# Core.net
KiCad netlist of a schematic drawn in Altium Designer
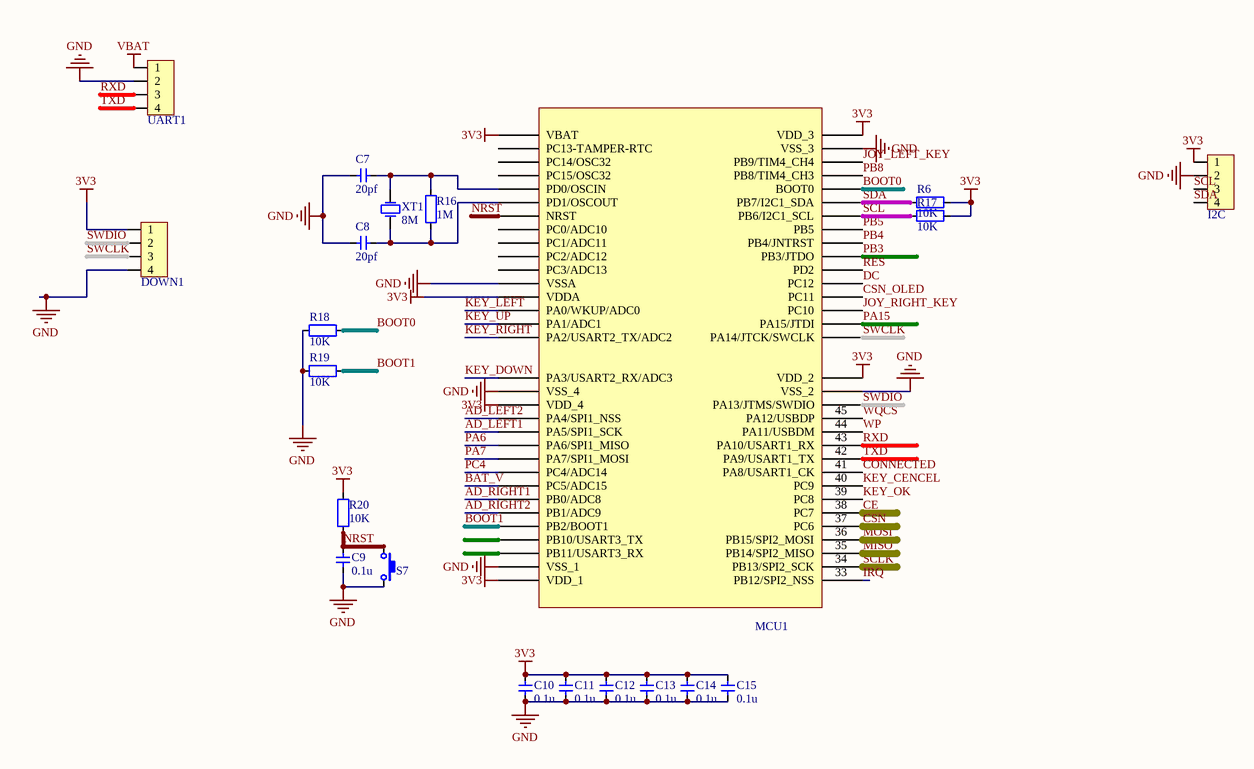
[diagram p0: Core.SchDoc]

(export (version "E")
  (design (tool "Eeschema 10.0.6"))
  (components
    (comp (ref "C7")
      (value "20pf")
      (footprint "PCB_PassiveCap:CAP_0603")
      (description "Capacitor")
      (fields (field (name "Comment") "Cap_0603"))
      (libsource (lib "SCH_Passive") (part "Cap_0603"))
    )
    (comp (ref "C8")
      (value "20pf")
      (footprint "PCB_PassiveCap:CAP_0603")
      (description "Capacitor")
      (fields (field (name "Comment") "Cap_0603"))
      (libsource (lib "SCH_Passive") (part "Cap_0603"))
    )
    (comp (ref "C9")
      (value "0.1u")
      (footprint "PCB_PassiveCap:CAP_0603")
      (description "Capacitor")
      (fields (field (name "Comment") "Cap_0603"))
      (libsource (lib "SCH_Passive") (part "Cap_0603"))
    )
    (comp (ref "C10")
      (value "0.1u")
      (footprint "PCB_PassiveCap:CAP_0603")
      (description "Capacitor")
      (fields (field (name "Comment") "Cap_0603"))
      (libsource (lib "SCH_Passive") (part "Cap_0603"))
    )
    (comp (ref "C11")
      (value "0.1u")
      (footprint "PCB_PassiveCap:CAP_0603")
      (description "Capacitor")
      (fields (field (name "Comment") "Cap_0603"))
      (libsource (lib "SCH_Passive") (part "Cap_0603"))
    )
    (comp (ref "C12")
      (value "0.1u")
      (footprint "PCB_PassiveCap:CAP_0603")
      (description "Capacitor")
      (fields (field (name "Comment") "Cap_0603"))
      (libsource (lib "SCH_Passive") (part "Cap_0603"))
    )
    (comp (ref "C13")
      (value "0.1u")
      (footprint "PCB_PassiveCap:CAP_0603")
      (description "Capacitor")
      (fields (field (name "Comment") "Cap_0603"))
      (libsource (lib "SCH_Passive") (part "Cap_0603"))
    )
    (comp (ref "C14")
      (value "0.1u")
      (footprint "PCB_PassiveCap:CAP_0603")
      (description "Capacitor")
      (fields (field (name "Comment") "Cap_0603"))
      (libsource (lib "SCH_Passive") (part "Cap_0603"))
    )
    (comp (ref "C15")
      (value "0.1u")
      (footprint "PCB_PassiveCap:CAP_0603")
      (description "Capacitor")
      (fields (field (name "Comment") "Cap_0603"))
      (libsource (lib "SCH_Passive") (part "Cap_0603"))
    )
    (comp (ref "DOWN1")
      (value "HDR1x4_2.54")
      (footprint "PCB_ConnectorHDR:HDR1x4_2.54_180")
      (description "Header")
      (libsource (lib "SCH_ConnectorHDR") (part "HDR1x4_2.54"))
    )
    (comp (ref "I2C")
      (value "HDR1x4_2.54")
      (footprint "PCB_ConnectorHDR:HDR1x4_2.54_180")
      (description "Header")
      (libsource (lib "SCH_ConnectorHDR") (part "HDR1x4_2.54"))
    )
    (comp (ref "MCU1")
      (value "STM32F103RC")
      (footprint "LQFP_P0.5_64")
      (description "MCU")
      (libsource (lib "SCH_IntegratedCircuit") (part "STM32F103RC"))
    )
    (comp (ref "R6")
      (value "10K")
      (footprint "PCB_PassiveRes:RES_0603")
      (description "Resistor")
      (fields (field (name "Comment") "Res_0603"))
      (libsource (lib "") (part "Res_0603_1"))
    )
    (comp (ref "R16")
      (value "1M")
      (footprint "PCB_PassiveRes:RES_0603")
      (description "Resistor")
      (fields (field (name "Comment") "Res_0603"))
      (libsource (lib "") (part "Res_0603_2"))
    )
    (comp (ref "R17")
      (value "10K")
      (footprint "PCB_PassiveRes:RES_0603")
      (description "Resistor")
      (fields (field (name "Comment") "Res_0603"))
      (libsource (lib "") (part "Res_0603_1"))
    )
    (comp (ref "R18")
      (value "10K")
      (footprint "PCB_PassiveRes:RES_0603")
      (description "Resistor")
      (fields (field (name "Comment") "Res_0603"))
      (libsource (lib "SCH_Passive") (part "Res_0603"))
    )
    (comp (ref "R19")
      (value "10K")
      (footprint "PCB_PassiveRes:RES_0603")
      (description "Resistor")
      (fields (field (name "Comment") "Res_0603"))
      (libsource (lib "SCH_Passive") (part "Res_0603"))
    )
    (comp (ref "R20")
      (value "10K")
      (footprint "PCB_PassiveRes:RES_0603")
      (description "Resistor")
      (fields (field (name "Comment") "Res_0603"))
      (libsource (lib "") (part "Res_0603_3"))
    )
    (comp (ref "S7")
      (value "ButtonTACT_3x4x2_180")
      (footprint "PCB_Switch:ButtonTACT_3x4x2_180H")
      (description "Button")
      (libsource (lib "SCH_Switch") (part "ButtonTACT_3x4x2_180"))
    )
    (comp (ref "UART1")
      (value "HDR1x4_2.54")
      (footprint "PCB_ConnectorHDR:HDR1x4_2.54_180")
      (description "Header")
      (libsource (lib "SCH_ConnectorHDR") (part "HDR1x4_2.54"))
    )
    (comp (ref "XT1")
      (value "8M")
      (footprint "PCB_Oscillator:XT_5032_2")
      (description "Crystal Oscillator")
      (fields (field (name "Comment") "XTAL_5032_2P"))
      (libsource (lib "SCH_Oscillator") (part "XTAL_5032_2P"))
    )
  )
  (nets
    (net (code "1") (name "/AD_LEFT1") (class "Default")
      (node (ref "MCU1") (pin "21") (pinfunction "PA5/SPI1_SCK_21") (pintype "passive"))
    )
    (net (code "2") (name "/AD_LEFT2") (class "Default")
      (node (ref "MCU1") (pin "20") (pinfunction "PA4/SPI1_NSS_20") (pintype "passive"))
    )
    (net (code "3") (name "/AD_RIGHT1") (class "Default")
      (node (ref "MCU1") (pin "26") (pinfunction "PB0/ADC8_26") (pintype "passive"))
    )
    (net (code "4") (name "/AD_RIGHT2") (class "Default")
      (node (ref "MCU1") (pin "27") (pinfunction "PB1/ADC9_27") (pintype "passive"))
    )
    (net (code "5") (name "/BAT_V") (class "Default")
      (node (ref "MCU1") (pin "25") (pinfunction "PC5/ADC15_25") (pintype "passive"))
    )
    (net (code "6") (name "/BOOT0") (class "Default")
      (node (ref "MCU1") (pin "60") (pinfunction "BOOT0_60") (pintype "passive"))
      (node (ref "R18") (pin "1") (pinfunction "1_1") (pintype "passive"))
    )
    (net (code "7") (name "/BOOT1") (class "Default")
      (node (ref "MCU1") (pin "28") (pinfunction "PB2/BOOT1_28") (pintype "passive"))
      (node (ref "R19") (pin "1") (pinfunction "1_1") (pintype "passive"))
    )
    (net (code "8") (name "/CE") (class "Default")
      (node (ref "MCU1") (pin "38") (pinfunction "PC7_38") (pintype "passive"))
    )
    (net (code "9") (name "/CONNECTED") (class "Default")
      (node (ref "MCU1") (pin "41") (pinfunction "PA8/USART1_CK_41") (pintype "passive"))
    )
    (net (code "10") (name "/CSN") (class "Default")
      (node (ref "MCU1") (pin "37") (pinfunction "PC6_37") (pintype "passive"))
    )
    (net (code "11") (name "/CSN_OLED") (class "Default")
      (node (ref "MCU1") (pin "52") (pinfunction "PC11_52") (pintype "passive"))
    )
    (net (code "12") (name "/DC") (class "Default")
      (node (ref "MCU1") (pin "53") (pinfunction "PC12_53") (pintype "passive"))
    )
    (net (code "13") (name "/IRQ") (class "Default")
      (node (ref "MCU1") (pin "33") (pinfunction "PB12/SPI2_NSS_33") (pintype "passive"))
    )
    (net (code "14") (name "/JOY_LEFT_KEY") (class "Default")
      (node (ref "MCU1") (pin "62") (pinfunction "PB9/TIM4_CH4_62") (pintype "passive"))
    )
    (net (code "15") (name "/JOY_RIGHT_KEY") (class "Default")
      (node (ref "MCU1") (pin "51") (pinfunction "PC10_51") (pintype "passive"))
    )
    (net (code "16") (name "/KEY_CENCEL") (class "Default")
      (node (ref "MCU1") (pin "40") (pinfunction "PC9_40") (pintype "passive"))
    )
    (net (code "17") (name "/KEY_DOWN") (class "Default")
      (node (ref "MCU1") (pin "17") (pinfunction "PA3/USART2_RX/ADC3_17") (pintype "passive"))
    )
    (net (code "18") (name "/KEY_LEFT") (class "Default")
      (node (ref "MCU1") (pin "14") (pinfunction "PA0/WKUP/ADC0_14") (pintype "passive"))
    )
    (net (code "19") (name "/KEY_OK") (class "Default")
      (node (ref "MCU1") (pin "39") (pinfunction "PC8_39") (pintype "passive"))
    )
    (net (code "20") (name "/KEY_RIGHT") (class "Default")
      (node (ref "MCU1") (pin "16") (pinfunction "PA2/USART2_TX/ADC2_16") (pintype "passive"))
    )
    (net (code "21") (name "/KEY_UP") (class "Default")
      (node (ref "MCU1") (pin "15") (pinfunction "PA1/ADC1_15") (pintype "passive"))
    )
    (net (code "22") (name "/MISO") (class "Default")
      (node (ref "MCU1") (pin "35") (pinfunction "PB14/SPI2_MISO_35") (pintype "passive"))
    )
    (net (code "23") (name "/MOSI") (class "Default")
      (node (ref "MCU1") (pin "36") (pinfunction "PB15/SPI2_MOSI_36") (pintype "passive"))
    )
    (net (code "24") (name "/NRST") (class "Default")
      (node (ref "C9") (pin "2") (pinfunction "2_2") (pintype "passive"))
      (node (ref "MCU1") (pin "7") (pinfunction "NRST_7") (pintype "passive"))
      (node (ref "R20") (pin "2") (pinfunction "2_2") (pintype "passive"))
      (node (ref "S7") (pin "1") (pinfunction "1_1") (pintype "passive"))
    )
    (net (code "25") (name "/PA6") (class "Default")
      (node (ref "MCU1") (pin "22") (pinfunction "PA6/SPI1_MISO_22") (pintype "passive"))
    )
    (net (code "26") (name "/PA7") (class "Default")
      (node (ref "MCU1") (pin "23") (pinfunction "PA7/SPI1_MOSI_23") (pintype "passive"))
    )
    (net (code "27") (name "/PA15") (class "Default")
      (node (ref "MCU1") (pin "50") (pinfunction "PA15/JTDI_50") (pintype "passive"))
    )
    (net (code "28") (name "/PB3") (class "Default")
      (node (ref "MCU1") (pin "55") (pinfunction "PB3/JTDO_55") (pintype "passive"))
    )
    (net (code "29") (name "/PB4") (class "Default")
      (node (ref "MCU1") (pin "56") (pinfunction "PB4/JNTRST_56") (pintype "passive"))
    )
    (net (code "30") (name "/PB5") (class "Default")
      (node (ref "MCU1") (pin "57") (pinfunction "PB5_57") (pintype "passive"))
    )
    (net (code "31") (name "/PB8") (class "Default")
      (node (ref "MCU1") (pin "61") (pinfunction "PB8/TIM4_CH3_61") (pintype "passive"))
    )
    (net (code "32") (name "/PC4") (class "Default")
      (node (ref "MCU1") (pin "24") (pinfunction "PC4/ADC14_24") (pintype "passive"))
    )
    (net (code "33") (name "/RES") (class "Default")
      (node (ref "MCU1") (pin "54") (pinfunction "PD2_54") (pintype "passive"))
    )
    (net (code "34") (name "/RXD") (class "Default")
      (node (ref "MCU1") (pin "43") (pinfunction "PA10/USART1_RX_43") (pintype "passive"))
      (node (ref "UART1") (pin "3") (pinfunction "3_3") (pintype "passive"))
    )
    (net (code "35") (name "/SCL") (class "Default")
      (node (ref "I2C") (pin "3") (pinfunction "3_3") (pintype "passive"))
      (node (ref "MCU1") (pin "58") (pinfunction "PB6/I2C1_SCL_58") (pintype "passive"))
      (node (ref "R17") (pin "1") (pinfunction "1_1") (pintype "passive"))
    )
    (net (code "36") (name "/SCLK") (class "Default")
      (node (ref "MCU1") (pin "34") (pinfunction "PB13/SPI2_SCK_34") (pintype "passive"))
    )
    (net (code "37") (name "/SDA") (class "Default")
      (node (ref "I2C") (pin "4") (pinfunction "4_4") (pintype "passive"))
      (node (ref "MCU1") (pin "59") (pinfunction "PB7/I2C1_SDA_59") (pintype "passive"))
      (node (ref "R6") (pin "1") (pinfunction "1_1") (pintype "passive"))
    )
    (net (code "38") (name "/SWCLK") (class "Default")
      (node (ref "DOWN1") (pin "3") (pinfunction "3_3") (pintype "passive"))
      (node (ref "MCU1") (pin "49") (pinfunction "PA14/JTCK/SWCLK_49") (pintype "passive"))
    )
    (net (code "39") (name "/SWDIO") (class "Default")
      (node (ref "DOWN1") (pin "2") (pinfunction "2_2") (pintype "passive"))
      (node (ref "MCU1") (pin "46") (pinfunction "PA13/JTMS/SWDIO_46") (pintype "passive"))
    )
    (net (code "40") (name "/TXD") (class "Default")
      (node (ref "MCU1") (pin "42") (pinfunction "PA9/USART1_TX_42") (pintype "passive"))
      (node (ref "UART1") (pin "4") (pinfunction "4_4") (pintype "passive"))
    )
    (net (code "41") (name "/WP") (class "Default")
      (node (ref "MCU1") (pin "44") (pinfunction "PA11/USBDM_44") (pintype "passive"))
    )
    (net (code "42") (name "/WQCS") (class "Default")
      (node (ref "MCU1") (pin "45") (pinfunction "PA12/USBDP_45") (pintype "passive"))
    )
    (net (code "43") (name "3V3") (class "Default")
      (node (ref "C10") (pin "2") (pinfunction "2_2") (pintype "passive"))
      (node (ref "C11") (pin "2") (pinfunction "2_2") (pintype "passive"))
      (node (ref "C12") (pin "2") (pinfunction "2_2") (pintype "passive"))
      (node (ref "C13") (pin "2") (pinfunction "2_2") (pintype "passive"))
      (node (ref "C14") (pin "2") (pinfunction "2_2") (pintype "passive"))
      (node (ref "C15") (pin "2") (pinfunction "2_2") (pintype "passive"))
      (node (ref "DOWN1") (pin "1") (pinfunction "1_1") (pintype "passive"))
      (node (ref "I2C") (pin "1") (pinfunction "1_1") (pintype "passive"))
      (node (ref "MCU1") (pin "1") (pinfunction "VBAT_1") (pintype "passive"))
      (node (ref "MCU1") (pin "13") (pinfunction "VDDA_13") (pintype "passive"))
      (node (ref "MCU1") (pin "19") (pinfunction "VDD_4_19") (pintype "passive"))
      (node (ref "MCU1") (pin "32") (pinfunction "VDD_1_32") (pintype "passive"))
      (node (ref "MCU1") (pin "48") (pinfunction "VDD_2_48") (pintype "passive"))
      (node (ref "MCU1") (pin "64") (pinfunction "VDD_3_64") (pintype "passive"))
      (node (ref "R17") (pin "2") (pinfunction "2_2") (pintype "passive"))
      (node (ref "R20") (pin "1") (pinfunction "1_1") (pintype "passive"))
      (node (ref "R6") (pin "2") (pinfunction "2_2") (pintype "passive"))
    )
    (net (code "44") (name "GND") (class "Default")
      (node (ref "C10") (pin "1") (pinfunction "1_1") (pintype "passive"))
      (node (ref "C11") (pin "1") (pinfunction "1_1") (pintype "passive"))
      (node (ref "C12") (pin "1") (pinfunction "1_1") (pintype "passive"))
      (node (ref "C13") (pin "1") (pinfunction "1_1") (pintype "passive"))
      (node (ref "C14") (pin "1") (pinfunction "1_1") (pintype "passive"))
      (node (ref "C15") (pin "1") (pinfunction "1_1") (pintype "passive"))
      (node (ref "C7") (pin "1") (pinfunction "1_1") (pintype "passive"))
      (node (ref "C8") (pin "1") (pinfunction "1_1") (pintype "passive"))
      (node (ref "C9") (pin "1") (pinfunction "1_1") (pintype "passive"))
      (node (ref "DOWN1") (pin "4") (pinfunction "4_4") (pintype "passive"))
      (node (ref "I2C") (pin "2") (pinfunction "2_2") (pintype "passive"))
      (node (ref "MCU1") (pin "12") (pinfunction "VSSA_12") (pintype "passive"))
      (node (ref "MCU1") (pin "18") (pinfunction "VSS_4_18") (pintype "passive"))
      (node (ref "MCU1") (pin "31") (pinfunction "VSS_1_31") (pintype "passive"))
      (node (ref "MCU1") (pin "47") (pinfunction "VSS_2_47") (pintype "passive"))
      (node (ref "MCU1") (pin "63") (pinfunction "VSS_3_63") (pintype "passive"))
      (node (ref "R18") (pin "2") (pinfunction "2_2") (pintype "passive"))
      (node (ref "R19") (pin "2") (pinfunction "2_2") (pintype "passive"))
      (node (ref "S7") (pin "2") (pinfunction "2_2") (pintype "passive"))
      (node (ref "UART1") (pin "2") (pinfunction "2_2") (pintype "passive"))
    )
    (net (code "45") (name "Net-(MCU1-PD0{slash}OSCIN)") (class "Default")
      (node (ref "C7") (pin "2") (pinfunction "2_2") (pintype "passive"))
      (node (ref "MCU1") (pin "5") (pinfunction "PD0/OSCIN_5") (pintype "passive"))
      (node (ref "R16") (pin "2") (pinfunction "2_2") (pintype "passive"))
      (node (ref "XT1") (pin "2") (pinfunction "OSC2_2") (pintype "passive"))
    )
    (net (code "46") (name "Net-(MCU1-PD1{slash}OSCOUT)") (class "Default")
      (node (ref "C8") (pin "2") (pinfunction "2_2") (pintype "passive"))
      (node (ref "MCU1") (pin "6") (pinfunction "PD1/OSCOUT_6") (pintype "passive"))
      (node (ref "R16") (pin "1") (pinfunction "1_1") (pintype "passive"))
      (node (ref "XT1") (pin "1") (pinfunction "OSC1_1") (pintype "passive"))
    )
    (net (code "47") (name "VBAT") (class "Default")
      (node (ref "UART1") (pin "1") (pinfunction "1_1") (pintype "passive"))
    )
    (net (code "48") (name "unconnected-(MCU1-PB10{slash}USART3_TX-Pad29)") (class "Default")
      (node (ref "MCU1") (pin "29") (pinfunction "PB10/USART3_TX_29") (pintype "passive"))
    )
    (net (code "49") (name "unconnected-(MCU1-PB11{slash}USART3_RX-Pad30)") (class "Default")
      (node (ref "MCU1") (pin "30") (pinfunction "PB11/USART3_RX_30") (pintype "passive"))
    )
    (net (code "50") (name "unconnected-(MCU1-PC0{slash}ADC10-Pad8)") (class "Default")
      (node (ref "MCU1") (pin "8") (pinfunction "PC0/ADC10_8") (pintype "passive"))
    )
    (net (code "51") (name "unconnected-(MCU1-PC1{slash}ADC11-Pad9)") (class "Default")
      (node (ref "MCU1") (pin "9") (pinfunction "PC1/ADC11_9") (pintype "passive"))
    )
    (net (code "52") (name "unconnected-(MCU1-PC2{slash}ADC12-Pad10)") (class "Default")
      (node (ref "MCU1") (pin "10") (pinfunction "PC2/ADC12_10") (pintype "passive"))
    )
    (net (code "53") (name "unconnected-(MCU1-PC3{slash}ADC13-Pad11)") (class "Default")
      (node (ref "MCU1") (pin "11") (pinfunction "PC3/ADC13_11") (pintype "passive"))
    )
    (net (code "54") (name "unconnected-(MCU1-PC13-TAMPER-RTC-Pad2)") (class "Default")
      (node (ref "MCU1") (pin "2") (pinfunction "PC13-TAMPER-RTC_2") (pintype "passive"))
    )
    (net (code "55") (name "unconnected-(MCU1-PC14{slash}OSC32-Pad3)") (class "Default")
      (node (ref "MCU1") (pin "3") (pinfunction "PC14/OSC32_3") (pintype "passive"))
    )
    (net (code "56") (name "unconnected-(MCU1-PC15{slash}OSC32-Pad4)") (class "Default")
      (node (ref "MCU1") (pin "4") (pinfunction "PC15/OSC32_4") (pintype "passive"))
    )
  )
)
